# AC_relay_board.net
KiCad netlist of a schematic drawn in EAGLE
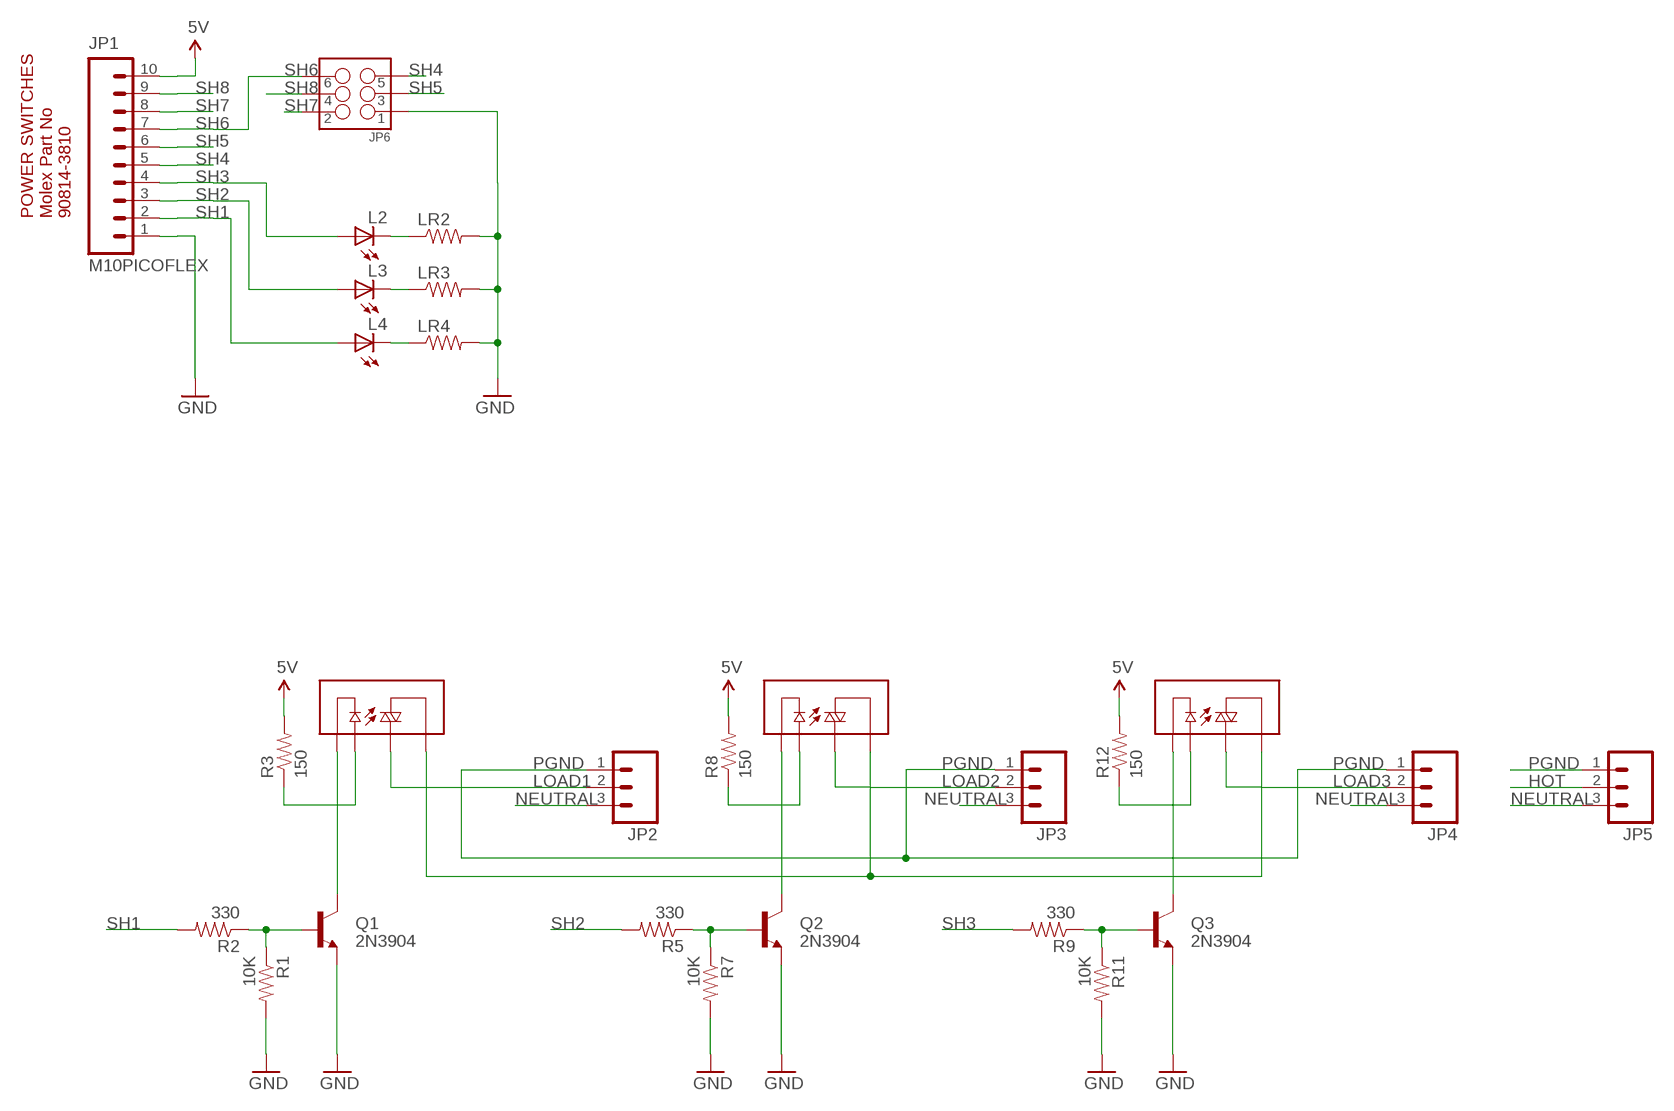
[diagram p0: schematic, sheet 1]

(export (version "E")
  (design (tool "Eeschema 10.0.6"))
  (components
    (comp (ref "JP1")
      (value "M10PICOFLEX")
      (footprint "eagle-import:CONNECTOR_MOLEX_PICOFLEX_10")
      (libsource (lib "eagle-import") (part "M10PICOFLEX"))
    )
    (comp (ref "JP2")
      (value "M03SCREW_LOCK")
      (footprint "eagle-import:SCREWTERMINAL-3.5MM-3_LOCK.007S")
      (libsource (lib "eagle-import") (part "M03SCREW_LOCK"))
    )
    (comp (ref "JP3")
      (value "M03SCREW_LOCK")
      (footprint "eagle-import:SCREWTERMINAL-3.5MM-3_LOCK.007S")
      (libsource (lib "eagle-import") (part "M03SCREW_LOCK"))
    )
    (comp (ref "JP4")
      (value "M03SCREW_LOCK")
      (footprint "eagle-import:SCREWTERMINAL-3.5MM-3_LOCK.007S")
      (libsource (lib "eagle-import") (part "M03SCREW_LOCK"))
    )
    (comp (ref "JP5")
      (value "M03SCREW_LOCK")
      (footprint "eagle-import:SCREWTERMINAL-3.5MM-3_LOCK.007S")
      (libsource (lib "eagle-import") (part "M03SCREW_LOCK"))
    )
    (comp (ref "JP6")
      (value "M03X2NO_SILK")
      (footprint "eagle-import:2X3-NS")
      (libsource (lib "eagle-import") (part "M03X2NO_SILK"))
    )
    (comp (ref "L2")
      (value "LED0805")
      (footprint "eagle-import:LED-0805")
      (libsource (lib "eagle-import") (part "LED0805"))
    )
    (comp (ref "L3")
      (value "LED0805")
      (footprint "eagle-import:LED-0805")
      (libsource (lib "eagle-import") (part "LED0805"))
    )
    (comp (ref "L4")
      (value "LED0805")
      (footprint "eagle-import:LED-0805")
      (libsource (lib "eagle-import") (part "LED0805"))
    )
    (comp (ref "LR2")
      (value "RESISTOR0805-RES")
      (footprint "eagle-import:0805")
      (libsource (lib "eagle-import") (part "SparkFun_RESISTOR0805-RES"))
    )
    (comp (ref "LR3")
      (value "RESISTOR0805-RES")
      (footprint "eagle-import:0805")
      (libsource (lib "eagle-import") (part "SparkFun_RESISTOR0805-RES"))
    )
    (comp (ref "LR4")
      (value "RESISTOR0805-RES")
      (footprint "eagle-import:0805")
      (libsource (lib "eagle-import") (part "SparkFun_RESISTOR0805-RES"))
    )
    (comp (ref "Q1")
      (value "2N3904")
      (footprint "eagle-import:SOT23")
      (libsource (lib "eagle-import") (part "TRANSISTOR_NPNSOT23"))
    )
    (comp (ref "Q2")
      (value "2N3904")
      (footprint "eagle-import:SOT23")
      (libsource (lib "eagle-import") (part "TRANSISTOR_NPNSOT23"))
    )
    (comp (ref "Q3")
      (value "2N3904")
      (footprint "eagle-import:SOT23")
      (libsource (lib "eagle-import") (part "TRANSISTOR_NPNSOT23"))
    )
    (comp (ref "R1")
      (value "10K")
      (footprint "eagle-import:0805")
      (libsource (lib "eagle-import") (part "RESISTOR0805-RES"))
    )
    (comp (ref "R2")
      (value "330")
      (footprint "eagle-import:0805")
      (libsource (lib "eagle-import") (part "RESISTOR0805-RES"))
    )
    (comp (ref "R3")
      (value "150")
      (footprint "eagle-import:0805")
      (libsource (lib "eagle-import") (part "RESISTOR0805-RES"))
    )
    (comp (ref "R5")
      (value "330")
      (footprint "eagle-import:0805")
      (libsource (lib "eagle-import") (part "RESISTOR0805-RES"))
    )
    (comp (ref "R7")
      (value "10K")
      (footprint "eagle-import:0805")
      (libsource (lib "eagle-import") (part "RESISTOR0805-RES"))
    )
    (comp (ref "R8")
      (value "150")
      (footprint "eagle-import:0805")
      (libsource (lib "eagle-import") (part "RESISTOR0805-RES"))
    )
    (comp (ref "R9")
      (value "330")
      (footprint "eagle-import:0805")
      (libsource (lib "eagle-import") (part "RESISTOR0805-RES"))
    )
    (comp (ref "R11")
      (value "10K")
      (footprint "eagle-import:0805")
      (libsource (lib "eagle-import") (part "RESISTOR0805-RES"))
    )
    (comp (ref "R12")
      (value "150")
      (footprint "eagle-import:0805")
      (libsource (lib "eagle-import") (part "RESISTOR0805-RES"))
    )
    (comp (ref "U1")
      (value "S108T02")
      (footprint "eagle-import:RELAY-S202S01F")
      (libsource (lib "eagle-import") (part "RELAY-SOLIDSTATENEWPTH"))
    )
    (comp (ref "U2")
      (value "S108T02")
      (footprint "eagle-import:RELAY-S202S01F")
      (libsource (lib "eagle-import") (part "RELAY-SOLIDSTATENEWPTH"))
    )
    (comp (ref "U3")
      (value "S108T02")
      (footprint "eagle-import:RELAY-S202S01F")
      (libsource (lib "eagle-import") (part "RELAY-SOLIDSTATENEWPTH"))
    )
  )
  (nets
    (net (code "1") (name "/HOT") (class "Default")
      (node (ref "JP5") (pin "2") (pinfunction "2_2") (pintype "passive"))
      (node (ref "U1") (pin "2") (pinfunction "T1_2") (pintype "bidirectional"))
      (node (ref "U2") (pin "2") (pinfunction "T1_2") (pintype "bidirectional"))
      (node (ref "U3") (pin "2") (pinfunction "T1_2") (pintype "bidirectional"))
    )
    (net (code "2") (name "/LOAD1") (class "Default")
      (node (ref "JP2") (pin "2") (pinfunction "2_2") (pintype "passive"))
      (node (ref "U1") (pin "1") (pinfunction "T2_1") (pintype "bidirectional"))
    )
    (net (code "3") (name "/LOAD2") (class "Default")
      (node (ref "JP3") (pin "2") (pinfunction "2_2") (pintype "passive"))
      (node (ref "U2") (pin "1") (pinfunction "T2_1") (pintype "bidirectional"))
    )
    (net (code "4") (name "/LOAD3") (class "Default")
      (node (ref "JP4") (pin "2") (pinfunction "2_2") (pintype "passive"))
      (node (ref "U3") (pin "1") (pinfunction "T2_1") (pintype "bidirectional"))
    )
    (net (code "5") (name "/NEUTRAL") (class "Default")
      (node (ref "JP2") (pin "3") (pinfunction "3_3") (pintype "passive"))
      (node (ref "JP3") (pin "3") (pinfunction "3_3") (pintype "passive"))
      (node (ref "JP4") (pin "3") (pinfunction "3_3") (pintype "passive"))
      (node (ref "JP5") (pin "3") (pinfunction "3_3") (pintype "passive"))
    )
    (net (code "6") (name "/PGND") (class "Default")
      (node (ref "JP2") (pin "1") (pinfunction "1_1") (pintype "passive"))
      (node (ref "JP3") (pin "1") (pinfunction "1_1") (pintype "passive"))
      (node (ref "JP4") (pin "1") (pinfunction "1_1") (pintype "passive"))
      (node (ref "JP5") (pin "1") (pinfunction "1_1") (pintype "passive"))
    )
    (net (code "7") (name "/SH1") (class "Default")
      (node (ref "JP1") (pin "2") (pinfunction "2_2") (pintype "passive"))
      (node (ref "L4") (pin "A+") (pinfunction "A_A+") (pintype "passive"))
      (node (ref "R2") (pin "2") (pinfunction "2_2") (pintype "passive"))
    )
    (net (code "8") (name "/SH2") (class "Default")
      (node (ref "JP1") (pin "3") (pinfunction "3_3") (pintype "passive"))
      (node (ref "L3") (pin "A+") (pinfunction "A_A+") (pintype "passive"))
      (node (ref "R5") (pin "2") (pinfunction "2_2") (pintype "passive"))
    )
    (net (code "9") (name "/SH3") (class "Default")
      (node (ref "JP1") (pin "4") (pinfunction "4_4") (pintype "passive"))
      (node (ref "L2") (pin "A+") (pinfunction "A_A+") (pintype "passive"))
      (node (ref "R9") (pin "2") (pinfunction "2_2") (pintype "passive"))
    )
    (net (code "10") (name "/SH4") (class "Default")
      (node (ref "JP1") (pin "5") (pinfunction "5_5") (pintype "passive"))
      (node (ref "JP6") (pin "5") (pinfunction "5_5") (pintype "bidirectional"))
    )
    (net (code "11") (name "/SH5") (class "Default")
      (node (ref "JP1") (pin "6") (pinfunction "6_6") (pintype "passive"))
      (node (ref "JP6") (pin "3") (pinfunction "3_3") (pintype "bidirectional"))
    )
    (net (code "12") (name "/SH6") (class "Default")
      (node (ref "JP1") (pin "7") (pinfunction "7_7") (pintype "passive"))
      (node (ref "JP6") (pin "6") (pinfunction "6_6") (pintype "bidirectional"))
    )
    (net (code "13") (name "/SH7") (class "Default")
      (node (ref "JP1") (pin "8") (pinfunction "8_8") (pintype "passive"))
      (node (ref "JP6") (pin "2") (pinfunction "2_2") (pintype "bidirectional"))
    )
    (net (code "14") (name "/SH8") (class "Default")
      (node (ref "JP1") (pin "9") (pinfunction "9_9") (pintype "passive"))
      (node (ref "JP6") (pin "4") (pinfunction "4_4") (pintype "bidirectional"))
    )
    (net (code "15") (name "5V") (class "Default")
      (node (ref "JP1") (pin "10") (pinfunction "10_10") (pintype "passive"))
      (node (ref "R12") (pin "2") (pinfunction "2_2") (pintype "passive"))
      (node (ref "R3") (pin "2") (pinfunction "2_2") (pintype "passive"))
      (node (ref "R8") (pin "2") (pinfunction "2_2") (pintype "passive"))
    )
    (net (code "16") (name "GND") (class "Default")
      (node (ref "JP1") (pin "1") (pinfunction "1_1") (pintype "passive"))
      (node (ref "JP6") (pin "1") (pinfunction "1_1") (pintype "bidirectional"))
      (node (ref "LR2") (pin "2") (pinfunction "2_2") (pintype "passive"))
      (node (ref "LR3") (pin "2") (pinfunction "2_2") (pintype "passive"))
      (node (ref "LR4") (pin "2") (pinfunction "2_2") (pintype "passive"))
      (node (ref "Q1") (pin "2") (pinfunction "E_2") (pintype "passive"))
      (node (ref "Q2") (pin "2") (pinfunction "E_2") (pintype "passive"))
      (node (ref "Q3") (pin "2") (pinfunction "E_2") (pintype "passive"))
      (node (ref "R1") (pin "2") (pinfunction "2_2") (pintype "passive"))
      (node (ref "R11") (pin "2") (pinfunction "2_2") (pintype "passive"))
      (node (ref "R7") (pin "2") (pinfunction "2_2") (pintype "passive"))
    )
    (net (code "17") (name "Net-(L2-C)") (class "Default")
      (node (ref "L2") (pin "C-") (pinfunction "C_C-") (pintype "passive"))
      (node (ref "LR2") (pin "1") (pinfunction "1_1") (pintype "passive"))
    )
    (net (code "18") (name "Net-(L3-C)") (class "Default")
      (node (ref "L3") (pin "C-") (pinfunction "C_C-") (pintype "passive"))
      (node (ref "LR3") (pin "1") (pinfunction "1_1") (pintype "passive"))
    )
    (net (code "19") (name "Net-(L4-C)") (class "Default")
      (node (ref "L4") (pin "C-") (pinfunction "C_C-") (pintype "passive"))
      (node (ref "LR4") (pin "1") (pinfunction "1_1") (pintype "passive"))
    )
    (net (code "20") (name "Net-(Q1-B)") (class "Default")
      (node (ref "Q1") (pin "1") (pinfunction "B_1") (pintype "passive"))
      (node (ref "R1") (pin "1") (pinfunction "1_1") (pintype "passive"))
      (node (ref "R2") (pin "1") (pinfunction "1_1") (pintype "passive"))
    )
    (net (code "21") (name "Net-(Q1-C)") (class "Default")
      (node (ref "Q1") (pin "3") (pinfunction "C_3") (pintype "passive"))
      (node (ref "U1") (pin "4") (pinfunction "-_4") (pintype "bidirectional"))
    )
    (net (code "22") (name "Net-(Q2-B)") (class "Default")
      (node (ref "Q2") (pin "1") (pinfunction "B_1") (pintype "passive"))
      (node (ref "R5") (pin "1") (pinfunction "1_1") (pintype "passive"))
      (node (ref "R7") (pin "1") (pinfunction "1_1") (pintype "passive"))
    )
    (net (code "23") (name "Net-(Q2-C)") (class "Default")
      (node (ref "Q2") (pin "3") (pinfunction "C_3") (pintype "passive"))
      (node (ref "U2") (pin "4") (pinfunction "-_4") (pintype "bidirectional"))
    )
    (net (code "24") (name "Net-(Q3-B)") (class "Default")
      (node (ref "Q3") (pin "1") (pinfunction "B_1") (pintype "passive"))
      (node (ref "R11") (pin "1") (pinfunction "1_1") (pintype "passive"))
      (node (ref "R9") (pin "1") (pinfunction "1_1") (pintype "passive"))
    )
    (net (code "25") (name "Net-(Q3-C)") (class "Default")
      (node (ref "Q3") (pin "3") (pinfunction "C_3") (pintype "passive"))
      (node (ref "U3") (pin "4") (pinfunction "-_4") (pintype "bidirectional"))
    )
    (net (code "26") (name "Net-(U1-+)") (class "Default")
      (node (ref "R3") (pin "1") (pinfunction "1_1") (pintype "passive"))
      (node (ref "U1") (pin "3") (pinfunction "+_3") (pintype "bidirectional"))
    )
    (net (code "27") (name "Net-(U2-+)") (class "Default")
      (node (ref "R8") (pin "1") (pinfunction "1_1") (pintype "passive"))
      (node (ref "U2") (pin "3") (pinfunction "+_3") (pintype "bidirectional"))
    )
    (net (code "28") (name "Net-(U3-+)") (class "Default")
      (node (ref "R12") (pin "1") (pinfunction "1_1") (pintype "passive"))
      (node (ref "U3") (pin "3") (pinfunction "+_3") (pintype "bidirectional"))
    )
  )
)
